# mubi-ESP32-38.net
KiCad netlist of a schematic drawn in EAGLE
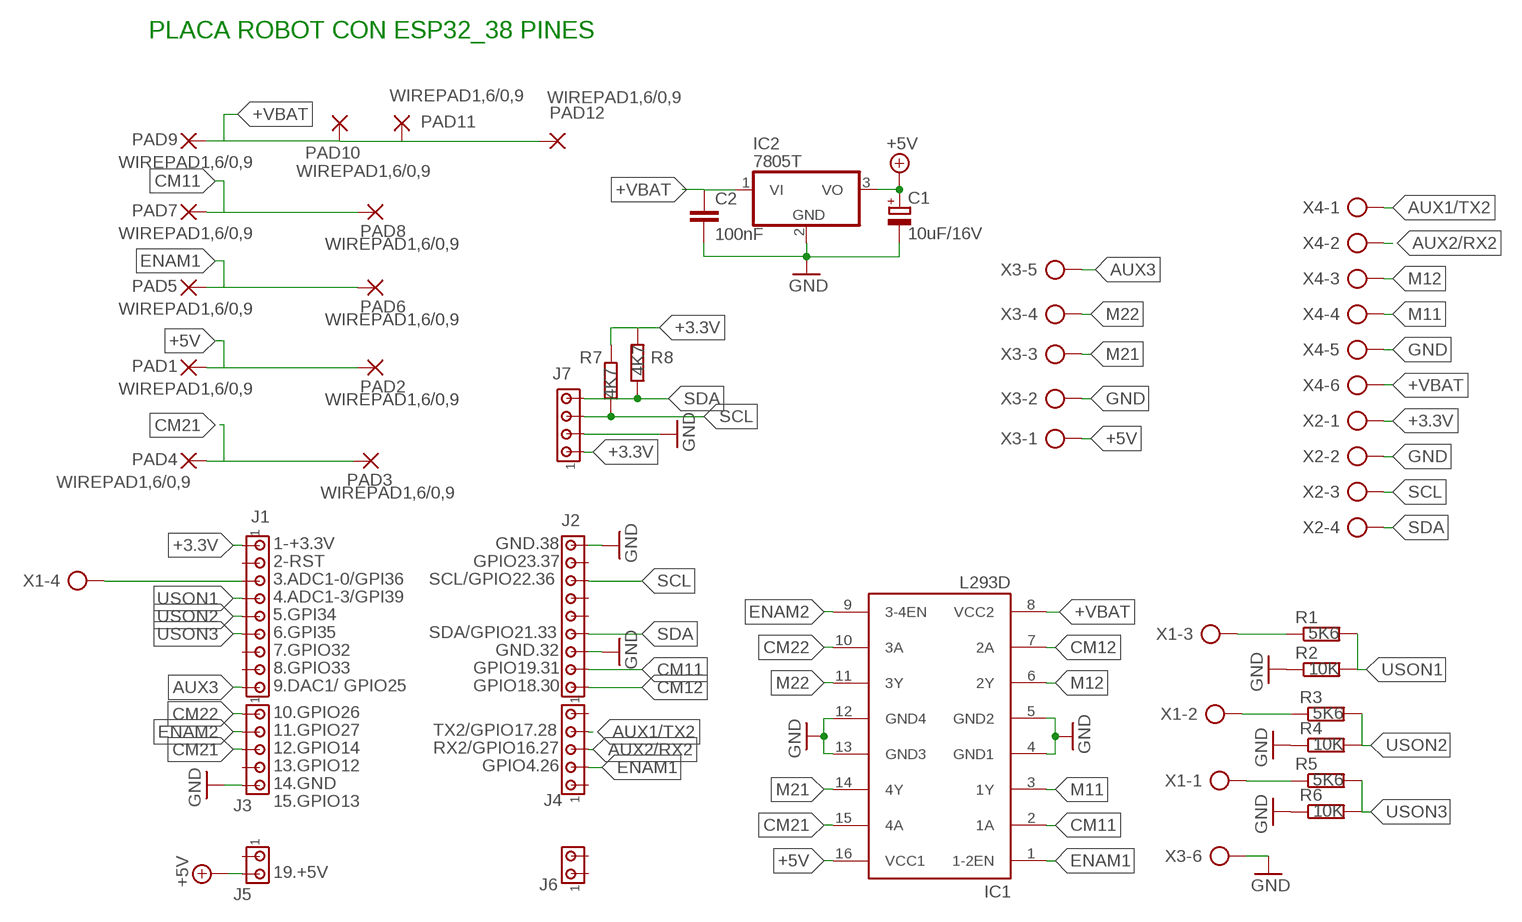
[diagram p0: schematic, sheet 1]

(export (version "E")
  (design (tool "Eeschema 10.0.6"))
  (components
    (comp (ref "C1")
      (value "10uF/16V")
      (footprint "eagle-import:E2,5-6")
      (libsource (lib "eagle-import") (part "CPOL-EUE2.5-6"))
    )
    (comp (ref "C2")
      (value "100nF")
      (footprint "eagle-import:C025-025X050")
      (libsource (lib "eagle-import") (part "C-EU025-025X050"))
    )
    (comp (ref "IC1")
      (value "L293D")
      (footprint "eagle-import:DIL16")
      (libsource (lib "eagle-import") (part "L293D"))
    )
    (comp (ref "IC2")
      (value "7805T")
      (footprint "eagle-import:TO220H")
      (libsource (lib "eagle-import") (part "78T05"))
    )
    (comp (ref "J1")
      (value "MTA09-100")
      (footprint "eagle-import:10X09MTA")
      (libsource (lib "eagle-import") (part "MTA09-100"))
    )
    (comp (ref "J2")
      (value "MTA09-100")
      (footprint "eagle-import:10X09MTA")
      (libsource (lib "eagle-import") (part "MTA09-100"))
    )
    (comp (ref "J3")
      (value "MTA05-100")
      (footprint "eagle-import:10X05MTA")
      (libsource (lib "eagle-import") (part "MTA05-100"))
    )
    (comp (ref "J4")
      (value "MTA05-100")
      (footprint "eagle-import:10X05MTA")
      (libsource (lib "eagle-import") (part "MTA05-100"))
    )
    (comp (ref "J5")
      (value "MTA02-100")
      (footprint "eagle-import:10X02MTA")
      (libsource (lib "eagle-import") (part "MTA02-100"))
    )
    (comp (ref "J6")
      (value "MTA02-100")
      (footprint "eagle-import:10X02MTA")
      (libsource (lib "eagle-import") (part "MTA02-100"))
    )
    (comp (ref "J7")
      (value "MTA04-100")
      (footprint "eagle-import:10X04MTA")
      (libsource (lib "eagle-import") (part "MTA04-100"))
    )
    (comp (ref "PAD1")
      (value "WIREPAD1,6/0,9")
      (footprint "eagle-import:1,6_0,9")
      (libsource (lib "eagle-import") (part "WIREPAD1,6/0,9"))
    )
    (comp (ref "PAD2")
      (value "WIREPAD1,6/0,9")
      (footprint "eagle-import:1,6_0,9")
      (libsource (lib "eagle-import") (part "WIREPAD1,6/0,9"))
    )
    (comp (ref "PAD3")
      (value "WIREPAD1,6/0,9")
      (footprint "eagle-import:1,6_0,9")
      (libsource (lib "eagle-import") (part "WIREPAD1,6/0,9"))
    )
    (comp (ref "PAD4")
      (value "WIREPAD1,6/0,9")
      (footprint "eagle-import:1,6_0,9")
      (libsource (lib "eagle-import") (part "WIREPAD1,6/0,9"))
    )
    (comp (ref "PAD5")
      (value "WIREPAD1,6/0,9")
      (footprint "eagle-import:1,6_0,9")
      (libsource (lib "eagle-import") (part "WIREPAD1,6/0,9"))
    )
    (comp (ref "PAD6")
      (value "WIREPAD1,6/0,9")
      (footprint "eagle-import:1,6_0,9")
      (libsource (lib "eagle-import") (part "WIREPAD1,6/0,9"))
    )
    (comp (ref "PAD7")
      (value "WIREPAD1,6/0,9")
      (footprint "eagle-import:1,6_0,9")
      (libsource (lib "eagle-import") (part "WIREPAD1,6/0,9"))
    )
    (comp (ref "PAD8")
      (value "WIREPAD1,6/0,9")
      (footprint "eagle-import:1,6_0,9")
      (libsource (lib "eagle-import") (part "WIREPAD1,6/0,9"))
    )
    (comp (ref "PAD9")
      (value "WIREPAD1,6/0,9")
      (footprint "eagle-import:1,6_0,9")
      (libsource (lib "eagle-import") (part "WIREPAD1,6/0,9"))
    )
    (comp (ref "PAD10")
      (value "WIREPAD1,6/0,9")
      (footprint "eagle-import:1,6_0,9")
      (libsource (lib "eagle-import") (part "WIREPAD1,6/0,9"))
    )
    (comp (ref "PAD11")
      (value "WIREPAD1,6/0,9")
      (footprint "eagle-import:1,6_0,9")
      (libsource (lib "eagle-import") (part "WIREPAD1,6/0,9"))
    )
    (comp (ref "PAD12")
      (value "WIREPAD1,6/0,9")
      (footprint "eagle-import:1,6_0,9")
      (libsource (lib "eagle-import") (part "WIREPAD1,6/0,9"))
    )
    (comp (ref "R1")
      (value "5K6")
      (footprint "eagle-import:0204_5")
      (libsource (lib "eagle-import") (part "R-EU_0204/5"))
    )
    (comp (ref "R2")
      (value "10K")
      (footprint "eagle-import:0204_5")
      (libsource (lib "eagle-import") (part "R-EU_0204/5"))
    )
    (comp (ref "R3")
      (value "5K6")
      (footprint "eagle-import:0204_5")
      (libsource (lib "eagle-import") (part "R-EU_0204/5"))
    )
    (comp (ref "R4")
      (value "10K")
      (footprint "eagle-import:0204_5")
      (libsource (lib "eagle-import") (part "R-EU_0204/5"))
    )
    (comp (ref "R5")
      (value "5K6")
      (footprint "eagle-import:0204_5")
      (libsource (lib "eagle-import") (part "R-EU_0204/5"))
    )
    (comp (ref "R6")
      (value "10K")
      (footprint "eagle-import:0204_5")
      (libsource (lib "eagle-import") (part "R-EU_0204/5"))
    )
    (comp (ref "R7")
      (value "4K7")
      (footprint "eagle-import:0207_7")
      (libsource (lib "eagle-import") (part "R-EU_0207/7"))
    )
    (comp (ref "R8")
      (value "4K7")
      (footprint "eagle-import:0207_7")
      (libsource (lib "eagle-import") (part "R-EU_0207/7"))
    )
    (comp (ref "X1")
      (value "AK500/4-H")
      (footprint "eagle-import:AK500_4-H")
      (libsource (lib "eagle-import") (part "AK500/4-H"))
    )
    (comp (ref "X2")
      (value "AK500/4-H")
      (footprint "eagle-import:AK500_4-H")
      (libsource (lib "eagle-import") (part "AK500/4-H"))
    )
    (comp (ref "X3")
      (value "AK500/6-H")
      (footprint "eagle-import:AK500_6-H")
      (libsource (lib "eagle-import") (part "AK500/6-H"))
    )
    (comp (ref "X4")
      (value "AK500/6-H")
      (footprint "eagle-import:AK500_6-H")
      (libsource (lib "eagle-import") (part "AK500/6-H"))
    )
  )
  (nets
    (net (code "1") (name "+3.3V") (class "Default")
      (node (ref "J1") (pin "1") (pinfunction "1_1") (pintype "passive"))
      (node (ref "J7") (pin "1") (pinfunction "1_1") (pintype "passive"))
      (node (ref "R7") (pin "2") (pinfunction "2_2") (pintype "passive"))
      (node (ref "R8") (pin "2") (pinfunction "2_2") (pintype "passive"))
      (node (ref "X2") (pin "1") (pinfunction "KL_1") (pintype "passive"))
    )
    (net (code "2") (name "+5V") (class "Default")
      (node (ref "C1") (pin "+") (pinfunction "+_+") (pintype "passive"))
      (node (ref "IC1") (pin "16") (pinfunction "VCC1_16") (pintype "power_in"))
      (node (ref "IC2") (pin "3") (pinfunction "VO_3") (pintype "passive"))
      (node (ref "J5") (pin "2") (pinfunction "2_2") (pintype "passive"))
      (node (ref "PAD1") (pin "1") (pinfunction "P_1") (pintype "passive"))
      (node (ref "PAD2") (pin "1") (pinfunction "P_1") (pintype "passive"))
      (node (ref "X3") (pin "1") (pinfunction "KL_1") (pintype "passive"))
    )
    (net (code "3") (name "+VBAT") (class "Default")
      (node (ref "C2") (pin "1") (pinfunction "1_1") (pintype "passive"))
      (node (ref "IC1") (pin "8") (pinfunction "VCC2_8") (pintype "power_in"))
      (node (ref "IC2") (pin "1") (pinfunction "VI_1") (pintype "input"))
      (node (ref "PAD10") (pin "1") (pinfunction "P_1") (pintype "passive"))
      (node (ref "PAD11") (pin "1") (pinfunction "P_1") (pintype "passive"))
      (node (ref "PAD12") (pin "1") (pinfunction "P_1") (pintype "passive"))
      (node (ref "PAD9") (pin "1") (pinfunction "P_1") (pintype "passive"))
      (node (ref "X4") (pin "6") (pinfunction "KL_6") (pintype "passive"))
    )
    (net (code "4") (name "AUX1{slash}TX2") (class "Default")
      (node (ref "J4") (pin "4") (pinfunction "4_4") (pintype "passive"))
      (node (ref "X4") (pin "1") (pinfunction "KL_1") (pintype "passive"))
    )
    (net (code "5") (name "AUX2{slash}RX2") (class "Default")
      (node (ref "J4") (pin "3") (pinfunction "3_3") (pintype "passive"))
      (node (ref "X4") (pin "2") (pinfunction "KL_2") (pintype "passive"))
    )
    (net (code "6") (name "AUX3") (class "Default")
      (node (ref "J1") (pin "9") (pinfunction "9_9") (pintype "passive"))
      (node (ref "X3") (pin "5") (pinfunction "KL_5") (pintype "passive"))
    )
    (net (code "7") (name "CM11") (class "Default")
      (node (ref "IC1") (pin "2") (pinfunction "1A_2") (pintype "input"))
      (node (ref "J2") (pin "2") (pinfunction "2_2") (pintype "passive"))
      (node (ref "PAD7") (pin "1") (pinfunction "P_1") (pintype "passive"))
      (node (ref "PAD8") (pin "1") (pinfunction "P_1") (pintype "passive"))
    )
    (net (code "8") (name "CM12") (class "Default")
      (node (ref "IC1") (pin "7") (pinfunction "2A_7") (pintype "input"))
      (node (ref "J2") (pin "1") (pinfunction "1_1") (pintype "passive"))
    )
    (net (code "9") (name "CM21") (class "Default")
      (node (ref "IC1") (pin "15") (pinfunction "4A_15") (pintype "input"))
      (node (ref "J3") (pin "3") (pinfunction "3_3") (pintype "passive"))
      (node (ref "PAD3") (pin "1") (pinfunction "P_1") (pintype "passive"))
      (node (ref "PAD4") (pin "1") (pinfunction "P_1") (pintype "passive"))
    )
    (net (code "10") (name "CM22") (class "Default")
      (node (ref "IC1") (pin "10") (pinfunction "3A_10") (pintype "input"))
      (node (ref "J3") (pin "1") (pinfunction "1_1") (pintype "passive"))
    )
    (net (code "11") (name "ENAM1") (class "Default")
      (node (ref "IC1") (pin "1") (pinfunction "1-2EN_1") (pintype "input"))
      (node (ref "J4") (pin "2") (pinfunction "2_2") (pintype "passive"))
      (node (ref "PAD5") (pin "1") (pinfunction "P_1") (pintype "passive"))
      (node (ref "PAD6") (pin "1") (pinfunction "P_1") (pintype "passive"))
    )
    (net (code "12") (name "ENAM2") (class "Default")
      (node (ref "IC1") (pin "9") (pinfunction "3-4EN_9") (pintype "input"))
      (node (ref "J3") (pin "2") (pinfunction "2_2") (pintype "passive"))
    )
    (net (code "13") (name "GND") (class "Default")
      (node (ref "C1") (pin "-") (pinfunction "-_-") (pintype "passive"))
      (node (ref "C2") (pin "2") (pinfunction "2_2") (pintype "passive"))
      (node (ref "IC1") (pin "12") (pinfunction "GND4_12") (pintype "power_in"))
      (node (ref "IC1") (pin "13") (pinfunction "GND3_13") (pintype "power_in"))
      (node (ref "IC1") (pin "4") (pinfunction "GND1_4") (pintype "power_in"))
      (node (ref "IC1") (pin "5") (pinfunction "GND2_5") (pintype "power_in"))
      (node (ref "IC2") (pin "2") (pinfunction "GND_2") (pintype "passive"))
      (node (ref "J2") (pin "3") (pinfunction "3_3") (pintype "passive"))
      (node (ref "J2") (pin "9") (pinfunction "9_9") (pintype "passive"))
      (node (ref "J3") (pin "5") (pinfunction "5_5") (pintype "passive"))
      (node (ref "J7") (pin "2") (pinfunction "2_2") (pintype "passive"))
      (node (ref "R2") (pin "1") (pinfunction "1_1") (pintype "passive"))
      (node (ref "R4") (pin "1") (pinfunction "1_1") (pintype "passive"))
      (node (ref "R6") (pin "1") (pinfunction "1_1") (pintype "passive"))
      (node (ref "X2") (pin "2") (pinfunction "KL_2") (pintype "passive"))
      (node (ref "X3") (pin "2") (pinfunction "KL_2") (pintype "passive"))
      (node (ref "X3") (pin "6") (pinfunction "KL_6") (pintype "passive"))
      (node (ref "X4") (pin "5") (pinfunction "KL_5") (pintype "passive"))
    )
    (net (code "14") (name "M11") (class "Default")
      (node (ref "IC1") (pin "3") (pinfunction "1Y_3") (pintype "output"))
      (node (ref "X4") (pin "4") (pinfunction "KL_4") (pintype "passive"))
    )
    (net (code "15") (name "M12") (class "Default")
      (node (ref "IC1") (pin "6") (pinfunction "2Y_6") (pintype "output"))
      (node (ref "X4") (pin "3") (pinfunction "KL_3") (pintype "passive"))
    )
    (net (code "16") (name "M21") (class "Default")
      (node (ref "IC1") (pin "14") (pinfunction "4Y_14") (pintype "output"))
      (node (ref "X3") (pin "3") (pinfunction "KL_3") (pintype "passive"))
    )
    (net (code "17") (name "M22") (class "Default")
      (node (ref "IC1") (pin "11") (pinfunction "3Y_11") (pintype "output"))
      (node (ref "X3") (pin "4") (pinfunction "KL_4") (pintype "passive"))
    )
    (net (code "18") (name "Net-(X1A-KL)") (class "Default")
      (node (ref "R5") (pin "1") (pinfunction "1_1") (pintype "passive"))
      (node (ref "X1") (pin "1") (pinfunction "KL_1") (pintype "passive"))
    )
    (net (code "19") (name "Net-(X1B-KL)") (class "Default")
      (node (ref "R3") (pin "1") (pinfunction "1_1") (pintype "passive"))
      (node (ref "X1") (pin "2") (pinfunction "KL_2") (pintype "passive"))
    )
    (net (code "20") (name "Net-(X1C-KL)") (class "Default")
      (node (ref "R1") (pin "1") (pinfunction "1_1") (pintype "passive"))
      (node (ref "X1") (pin "3") (pinfunction "KL_3") (pintype "passive"))
    )
    (net (code "21") (name "Net-(X1D-KL)") (class "Default")
      (node (ref "J1") (pin "3") (pinfunction "3_3") (pintype "passive"))
      (node (ref "X1") (pin "4") (pinfunction "KL_4") (pintype "passive"))
    )
    (net (code "22") (name "SCL") (class "Default")
      (node (ref "J2") (pin "7") (pinfunction "7_7") (pintype "passive"))
      (node (ref "J7") (pin "3") (pinfunction "3_3") (pintype "passive"))
      (node (ref "R7") (pin "1") (pinfunction "1_1") (pintype "passive"))
      (node (ref "X2") (pin "3") (pinfunction "KL_3") (pintype "passive"))
    )
    (net (code "23") (name "SDA") (class "Default")
      (node (ref "J2") (pin "4") (pinfunction "4_4") (pintype "passive"))
      (node (ref "J7") (pin "4") (pinfunction "4_4") (pintype "passive"))
      (node (ref "R8") (pin "1") (pinfunction "1_1") (pintype "passive"))
      (node (ref "X2") (pin "4") (pinfunction "KL_4") (pintype "passive"))
    )
    (net (code "24") (name "USON1") (class "Default")
      (node (ref "J1") (pin "4") (pinfunction "4_4") (pintype "passive"))
      (node (ref "R1") (pin "2") (pinfunction "2_2") (pintype "passive"))
      (node (ref "R2") (pin "2") (pinfunction "2_2") (pintype "passive"))
    )
    (net (code "25") (name "USON2") (class "Default")
      (node (ref "J1") (pin "5") (pinfunction "5_5") (pintype "passive"))
      (node (ref "R3") (pin "2") (pinfunction "2_2") (pintype "passive"))
      (node (ref "R4") (pin "2") (pinfunction "2_2") (pintype "passive"))
    )
    (net (code "26") (name "USON3") (class "Default")
      (node (ref "J1") (pin "6") (pinfunction "6_6") (pintype "passive"))
      (node (ref "R5") (pin "2") (pinfunction "2_2") (pintype "passive"))
      (node (ref "R6") (pin "2") (pinfunction "2_2") (pintype "passive"))
    )
    (net (code "27") (name "unconnected-(J1-Pad2)") (class "Default")
      (node (ref "J1") (pin "2") (pinfunction "2_2") (pintype "passive"))
    )
    (net (code "28") (name "unconnected-(J1-Pad7)") (class "Default")
      (node (ref "J1") (pin "7") (pinfunction "7_7") (pintype "passive"))
    )
    (net (code "29") (name "unconnected-(J1-Pad8)") (class "Default")
      (node (ref "J1") (pin "8") (pinfunction "8_8") (pintype "passive"))
    )
    (net (code "30") (name "unconnected-(J2-Pad5)") (class "Default")
      (node (ref "J2") (pin "5") (pinfunction "5_5") (pintype "passive"))
    )
    (net (code "31") (name "unconnected-(J2-Pad6)") (class "Default")
      (node (ref "J2") (pin "6") (pinfunction "6_6") (pintype "passive"))
    )
    (net (code "32") (name "unconnected-(J2-Pad8)") (class "Default")
      (node (ref "J2") (pin "8") (pinfunction "8_8") (pintype "passive"))
    )
    (net (code "33") (name "unconnected-(J3-Pad4)") (class "Default")
      (node (ref "J3") (pin "4") (pinfunction "4_4") (pintype "passive"))
    )
    (net (code "34") (name "unconnected-(J4-Pad1)") (class "Default")
      (node (ref "J4") (pin "1") (pinfunction "1_1") (pintype "passive"))
    )
    (net (code "35") (name "unconnected-(J4-Pad5)") (class "Default")
      (node (ref "J4") (pin "5") (pinfunction "5_5") (pintype "passive"))
    )
    (net (code "36") (name "unconnected-(J5-Pad1)") (class "Default")
      (node (ref "J5") (pin "1") (pinfunction "1_1") (pintype "passive"))
    )
    (net (code "37") (name "unconnected-(J6-Pad1)") (class "Default")
      (node (ref "J6") (pin "1") (pinfunction "1_1") (pintype "passive"))
    )
    (net (code "38") (name "unconnected-(J6-Pad2)") (class "Default")
      (node (ref "J6") (pin "2") (pinfunction "2_2") (pintype "passive"))
    )
  )
)
